# Papilio_WM.net
KiCad netlist of a schematic drawn in Altium Designer
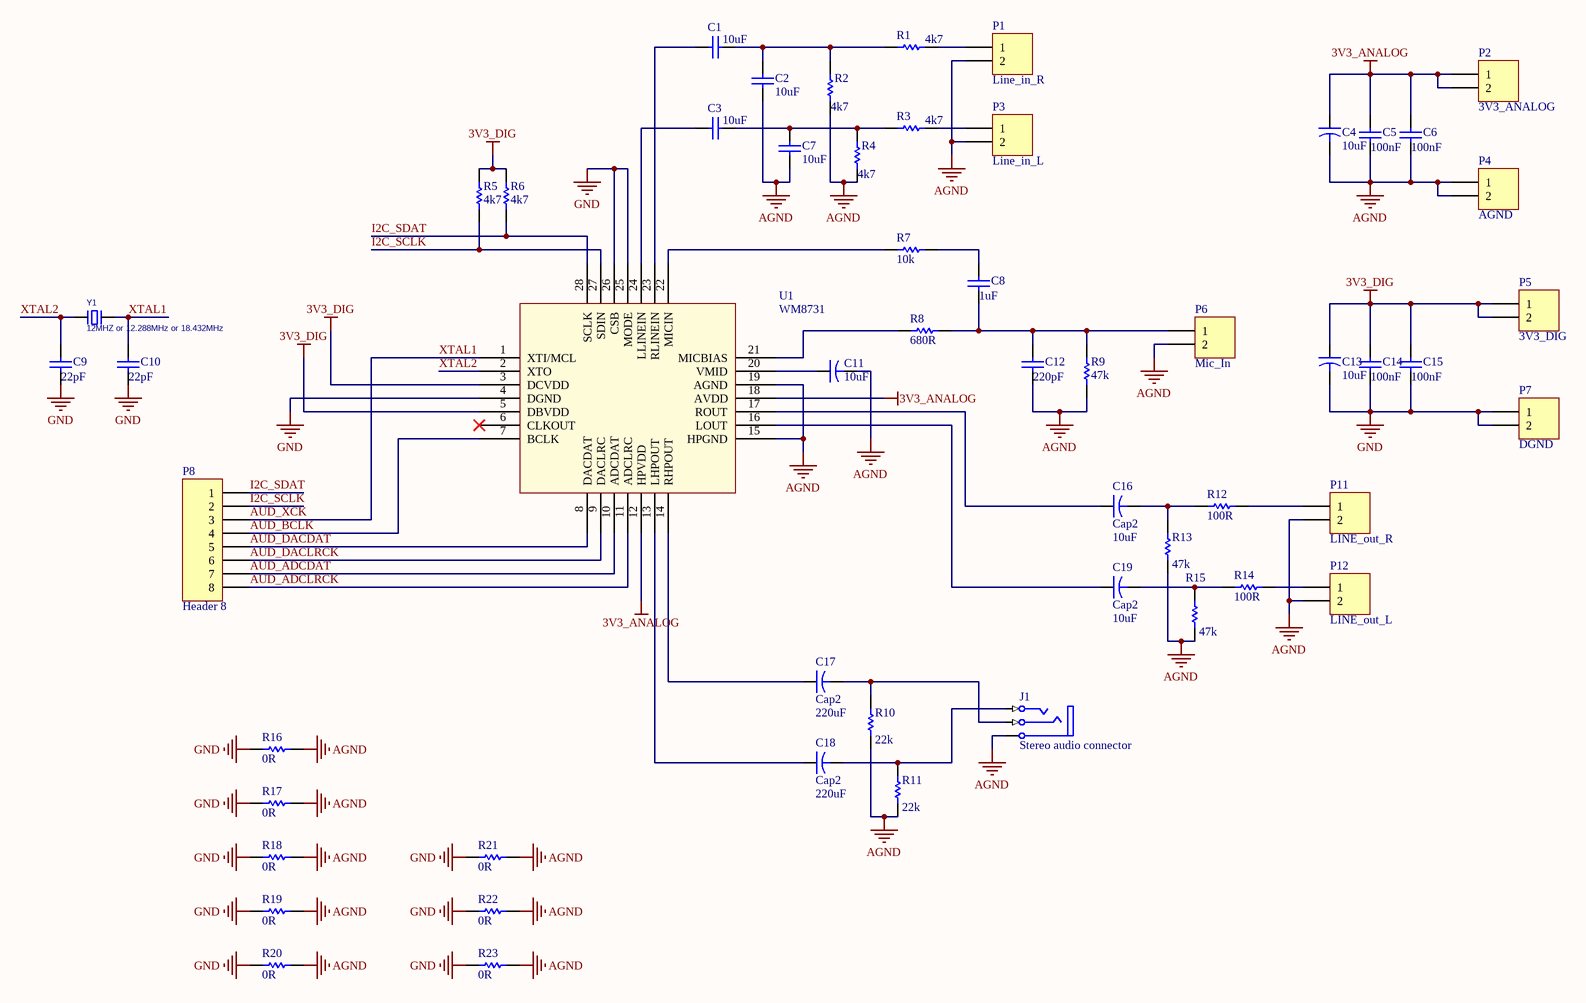
[diagram p0: Papilio_WM.SchDoc]

(export (version "E")
  (design (tool "Eeschema 10.0.6"))
  (components
    (comp (ref "C1")
      (value "10uF")
      (footprint "C0603 - rounded")
      (description "Capacitor")
      (fields (field (name "Comment") "Cap") (field (name "PUBLISHER") "Altium Limited"))
      (libsource (lib "Miscellaneous Devices") (part "Cap"))
    )
    (comp (ref "C2")
      (value "10uF")
      (footprint "C0603 - rounded")
      (description "Capacitor")
      (fields (field (name "Comment") "Cap") (field (name "PUBLISHER") "Altium Limited"))
      (libsource (lib "Miscellaneous Devices") (part "Cap"))
    )
    (comp (ref "C3")
      (value "10uF")
      (footprint "C0603 - rounded")
      (description "Capacitor")
      (fields (field (name "Comment") "Cap") (field (name "PUBLISHER") "Altium Limited"))
      (libsource (lib "Miscellaneous Devices") (part "Cap"))
    )
    (comp (ref "C4")
      (value "10uF")
      (footprint "CAP Eletrolitico 4x5.3 SMD")
      (description "Capacitor")
      (fields (field (name "Comment") "Cap2") (field (name "PUBLISHER") "Altium Limited"))
      (libsource (lib "Miscellaneous Devices") (part "Cap2"))
    )
    (comp (ref "C5")
      (value "100nF")
      (footprint "C0603 - rounded")
      (description "Capacitor")
      (fields (field (name "Comment") "Cap") (field (name "PUBLISHER") "Altium Limited"))
      (libsource (lib "Miscellaneous Devices") (part "Cap"))
    )
    (comp (ref "C6")
      (value "100nF")
      (footprint "C0603 - rounded")
      (description "Capacitor")
      (fields (field (name "Comment") "Cap") (field (name "PUBLISHER") "Altium Limited"))
      (libsource (lib "Miscellaneous Devices") (part "Cap"))
    )
    (comp (ref "C7")
      (value "10uF")
      (footprint "C0603 - rounded")
      (description "Capacitor")
      (fields (field (name "Comment") "Cap") (field (name "PUBLISHER") "Altium Limited"))
      (libsource (lib "Miscellaneous Devices") (part "Cap"))
    )
    (comp (ref "C8")
      (value "1uF")
      (footprint "C0603 - rounded")
      (description "Capacitor")
      (fields (field (name "Comment") "Cap") (field (name "PUBLISHER") "Altium Limited"))
      (libsource (lib "Miscellaneous Devices") (part "Cap"))
    )
    (comp (ref "C9")
      (value "22pF")
      (footprint "C0603 - rounded")
      (description "Capacitor")
      (fields (field (name "Comment") "Cap") (field (name "PUBLISHER") "Altium Limited"))
      (libsource (lib "Miscellaneous Devices") (part "Cap"))
    )
    (comp (ref "C10")
      (value "22pF")
      (footprint "C0603 - rounded")
      (description "Capacitor")
      (fields (field (name "Comment") "Cap") (field (name "PUBLISHER") "Altium Limited"))
      (libsource (lib "Miscellaneous Devices") (part "Cap"))
    )
    (comp (ref "C11")
      (value "10uF")
      (footprint "CAP Eletrolitico 4x5.3 SMD")
      (description "Capacitor")
      (fields (field (name "Comment") "Cap2") (field (name "PUBLISHER") "Altium Limited"))
      (libsource (lib "Miscellaneous Devices") (part "Cap2"))
    )
    (comp (ref "C12")
      (value "220pF")
      (footprint "C0603 - rounded")
      (description "Capacitor")
      (fields (field (name "Comment") "Cap") (field (name "PUBLISHER") "Altium Limited"))
      (libsource (lib "Miscellaneous Devices") (part "Cap"))
    )
    (comp (ref "C13")
      (value "10uF")
      (footprint "CAP Eletrolitico 4x5.3 SMD")
      (description "Capacitor")
      (fields (field (name "Comment") "Cap2") (field (name "PUBLISHER") "Altium Limited"))
      (libsource (lib "Miscellaneous Devices") (part "Cap2"))
    )
    (comp (ref "C14")
      (value "100nF")
      (footprint "C0603 - rounded")
      (description "Capacitor")
      (fields (field (name "Comment") "Cap") (field (name "PUBLISHER") "Altium Limited"))
      (libsource (lib "Miscellaneous Devices") (part "Cap"))
    )
    (comp (ref "C15")
      (value "100nF")
      (footprint "C0603 - rounded")
      (description "Capacitor")
      (fields (field (name "Comment") "Cap") (field (name "PUBLISHER") "Altium Limited"))
      (libsource (lib "Miscellaneous Devices") (part "Cap"))
    )
    (comp (ref "C16")
      (value "Cap2")
      (footprint "CAP Eletrolitico 4x5.3 SMD")
      (description "Capacitor")
      (fields (field (name "ALTIUM_VALUE") "10uF") (field (name "PUBLISHER") "Altium Limited"))
      (libsource (lib "Miscellaneous Devices") (part "Cap2"))
    )
    (comp (ref "C17")
      (value "Cap2")
      (footprint "CAP Eletrolitico 4x5.3 SMD")
      (description "Capacitor")
      (fields (field (name "ALTIUM_VALUE") "220uF") (field (name "PUBLISHER") "Altium Limited"))
      (libsource (lib "Miscellaneous Devices") (part "Cap2"))
    )
    (comp (ref "C18")
      (value "Cap2")
      (footprint "CAP Eletrolitico 4x5.3 SMD")
      (description "Capacitor")
      (fields (field (name "ALTIUM_VALUE") "220uF") (field (name "PUBLISHER") "Altium Limited"))
      (libsource (lib "Miscellaneous Devices") (part "Cap2"))
    )
    (comp (ref "C19")
      (value "Cap2")
      (footprint "CAP Eletrolitico 4x5.3 SMD")
      (description "Capacitor")
      (fields (field (name "ALTIUM_VALUE") "10uF") (field (name "PUBLISHER") "Altium Limited"))
      (libsource (lib "Miscellaneous Devices") (part "Cap2"))
    )
    (comp (ref "J1")
      (value "Stereo audio connector")
      (footprint "Headphone plug")
      (libsource (lib "Biblioteca_pessoal") (part "Phonejack 3"))
    )
    (comp (ref "P1")
      (value "Line_in_R")
      (footprint "HDR1X2 signed")
      (description "Header, 2-Pin")
      (fields (field (name "PUBLISHER") "Altium Limited"))
      (libsource (lib "Miscellaneous Connectors") (part "Header 2"))
    )
    (comp (ref "P2")
      (value "3V3_ANALOG")
      (footprint "HDR1X2")
      (description "Header, 2-Pin")
      (fields (field (name "PUBLISHER") "Altium Limited"))
      (libsource (lib "Miscellaneous Connectors") (part "Header 2"))
    )
    (comp (ref "P3")
      (value "Line_in_L")
      (footprint "HDR1X2 signed")
      (description "Header, 2-Pin")
      (fields (field (name "PUBLISHER") "Altium Limited"))
      (libsource (lib "Miscellaneous Connectors") (part "Header 2"))
    )
    (comp (ref "P4")
      (value "AGND")
      (footprint "HDR1X2")
      (description "Header, 2-Pin")
      (fields (field (name "PUBLISHER") "Altium Limited"))
      (libsource (lib "Miscellaneous Connectors") (part "Header 2"))
    )
    (comp (ref "P5")
      (value "3V3_DIG")
      (footprint "HDR1X2")
      (description "Header, 2-Pin")
      (fields (field (name "PUBLISHER") "Altium Limited"))
      (libsource (lib "Miscellaneous Connectors") (part "Header 2"))
    )
    (comp (ref "P6")
      (value "Mic_In")
      (footprint "HDR1X2 signed")
      (description "Header, 2-Pin")
      (fields (field (name "PUBLISHER") "Altium Limited"))
      (libsource (lib "Miscellaneous Connectors") (part "Header 2"))
    )
    (comp (ref "P7")
      (value "DGND")
      (footprint "HDR1X2")
      (description "Header, 2-Pin")
      (fields (field (name "PUBLISHER") "Altium Limited"))
      (libsource (lib "Miscellaneous Connectors") (part "Header 2"))
    )
    (comp (ref "P8")
      (value "Header 8")
      (footprint "HDR1X8")
      (description "Header, 8-Pin")
      (fields (field (name "PUBLISHER") "Altium Limited"))
      (libsource (lib "Miscellaneous Connectors") (part "Header 8"))
    )
    (comp (ref "P11")
      (value "LINE_out_R")
      (footprint "HDR1X2 signed")
      (description "Header, 2-Pin")
      (fields (field (name "PUBLISHER") "Altium Limited"))
      (libsource (lib "Miscellaneous Connectors") (part "Header 2"))
    )
    (comp (ref "P12")
      (value "LINE_out_L")
      (footprint "HDR1X2 signed")
      (description "Header, 2-Pin")
      (fields (field (name "PUBLISHER") "Altium Limited"))
      (libsource (lib "Miscellaneous Connectors") (part "Header 2"))
    )
    (comp (ref "R1")
      (value "4k7")
      (footprint "R0603 - rounded")
      (description "Resistor")
      (fields (field (name "Comment") "Res1") (field (name "PUBLISHER") "Altium Limited"))
      (libsource (lib "Miscellaneous Devices") (part "Res1"))
    )
    (comp (ref "R2")
      (value "4k7")
      (footprint "R0603 - rounded")
      (description "Resistor")
      (fields (field (name "Comment") "Res1") (field (name "PUBLISHER") "Altium Limited"))
      (libsource (lib "Miscellaneous Devices") (part "Res1"))
    )
    (comp (ref "R3")
      (value "4k7")
      (footprint "R0603 - rounded")
      (description "Resistor")
      (fields (field (name "Comment") "Res1") (field (name "PUBLISHER") "Altium Limited"))
      (libsource (lib "Miscellaneous Devices") (part "Res1"))
    )
    (comp (ref "R4")
      (value "4k7")
      (footprint "R0603 - rounded")
      (description "Resistor")
      (fields (field (name "Comment") "Res1") (field (name "PUBLISHER") "Altium Limited"))
      (libsource (lib "Miscellaneous Devices") (part "Res1"))
    )
    (comp (ref "R5")
      (value "4k7")
      (footprint "R0603 - rounded")
      (description "Resistor")
      (fields (field (name "Comment") "Res1") (field (name "PUBLISHER") "Altium Limited"))
      (libsource (lib "Miscellaneous Devices") (part "Res1"))
    )
    (comp (ref "R6")
      (value "4k7")
      (footprint "R0603 - rounded")
      (description "Resistor")
      (fields (field (name "Comment") "Res1") (field (name "PUBLISHER") "Altium Limited"))
      (libsource (lib "Miscellaneous Devices") (part "Res1"))
    )
    (comp (ref "R7")
      (value "10k")
      (footprint "R0603 - rounded")
      (description "Resistor")
      (fields (field (name "Comment") "Res1") (field (name "PUBLISHER") "Altium Limited"))
      (libsource (lib "Miscellaneous Devices") (part "Res1"))
    )
    (comp (ref "R8")
      (value "680R")
      (footprint "R0603 - rounded")
      (description "Resistor")
      (fields (field (name "Comment") "Res1") (field (name "PUBLISHER") "Altium Limited"))
      (libsource (lib "Miscellaneous Devices") (part "Res1"))
    )
    (comp (ref "R9")
      (value "47k")
      (footprint "R0603 - rounded")
      (description "Resistor")
      (fields (field (name "Comment") "Res1") (field (name "PUBLISHER") "Altium Limited"))
      (libsource (lib "Miscellaneous Devices") (part "Res1"))
    )
    (comp (ref "R10")
      (value "22k")
      (footprint "R0603 - rounded")
      (description "Resistor")
      (fields (field (name "Comment") "Res1") (field (name "PUBLISHER") "Altium Limited"))
      (libsource (lib "Miscellaneous Devices") (part "Res1"))
    )
    (comp (ref "R11")
      (value "22k")
      (footprint "R0603 - rounded")
      (description "Resistor")
      (fields (field (name "Comment") "Res1") (field (name "PUBLISHER") "Altium Limited"))
      (libsource (lib "Miscellaneous Devices") (part "Res1"))
    )
    (comp (ref "R12")
      (value "100R")
      (footprint "R0603 - rounded")
      (description "Resistor")
      (fields (field (name "Comment") "Res1") (field (name "PUBLISHER") "Altium Limited"))
      (libsource (lib "Miscellaneous Devices") (part "Res1"))
    )
    (comp (ref "R13")
      (value "47k")
      (footprint "R0603 - rounded")
      (description "Resistor")
      (fields (field (name "Comment") "Res1") (field (name "PUBLISHER") "Altium Limited"))
      (libsource (lib "Miscellaneous Devices") (part "Res1"))
    )
    (comp (ref "R14")
      (value "100R")
      (footprint "R0603 - rounded")
      (description "Resistor")
      (fields (field (name "Comment") "Res1") (field (name "PUBLISHER") "Altium Limited"))
      (libsource (lib "Miscellaneous Devices") (part "Res1"))
    )
    (comp (ref "R15")
      (value "47k")
      (footprint "R0603 - rounded")
      (description "Resistor")
      (fields (field (name "Comment") "Res1") (field (name "PUBLISHER") "Altium Limited"))
      (libsource (lib "Miscellaneous Devices") (part "Res1"))
    )
    (comp (ref "R16")
      (value "0R")
      (footprint "R0603 - rounded")
      (description "Resistor")
      (fields (field (name "Comment") "Res1") (field (name "PUBLISHER") "Altium Limited"))
      (libsource (lib "Miscellaneous Devices") (part "Res1"))
    )
    (comp (ref "R17")
      (value "0R")
      (footprint "R0603 - rounded")
      (description "Resistor")
      (fields (field (name "Comment") "Res1") (field (name "PUBLISHER") "Altium Limited"))
      (libsource (lib "Miscellaneous Devices") (part "Res1"))
    )
    (comp (ref "R18")
      (value "0R")
      (footprint "R0603 - rounded")
      (description "Resistor")
      (fields (field (name "Comment") "Res1") (field (name "PUBLISHER") "Altium Limited"))
      (libsource (lib "Miscellaneous Devices") (part "Res1"))
    )
    (comp (ref "R19")
      (value "0R")
      (footprint "R0603 - rounded")
      (description "Resistor")
      (fields (field (name "Comment") "Res1") (field (name "PUBLISHER") "Altium Limited"))
      (libsource (lib "Miscellaneous Devices") (part "Res1"))
    )
    (comp (ref "R20")
      (value "0R")
      (footprint "R0603 - rounded")
      (description "Resistor")
      (fields (field (name "Comment") "Res1") (field (name "PUBLISHER") "Altium Limited"))
      (libsource (lib "Miscellaneous Devices") (part "Res1"))
    )
    (comp (ref "R21")
      (value "0R")
      (footprint "R0603 - rounded")
      (description "Resistor")
      (fields (field (name "Comment") "Res1") (field (name "PUBLISHER") "Altium Limited"))
      (libsource (lib "Miscellaneous Devices") (part "Res1"))
    )
    (comp (ref "R22")
      (value "0R")
      (footprint "R0603 - rounded")
      (description "Resistor")
      (fields (field (name "Comment") "Res1") (field (name "PUBLISHER") "Altium Limited"))
      (libsource (lib "Miscellaneous Devices") (part "Res1"))
    )
    (comp (ref "R23")
      (value "0R")
      (footprint "R0603 - rounded")
      (description "Resistor")
      (fields (field (name "Comment") "Res1") (field (name "PUBLISHER") "Altium Limited"))
      (libsource (lib "Miscellaneous Devices") (part "Res1"))
    )
    (comp (ref "U1")
      (value "WM8731")
      (footprint "QFN24")
      (description "Audio CODEC")
      (libsource (lib "Biblioteca_pessoal") (part "WM8731"))
    )
    (comp (ref "Y1")
      (value "12MHZ or 12.288MHz or 18.432MHz")
      (footprint "XTAL")
      (libsource (lib "Biblioteca_pessoal") (part "XD-49US-A"))
    )
  )
  (nets
    (net (code "1") (name "/AUD_ADCDAT") (class "Default")
      (node (ref "P8") (pin "7") (pinfunction "7_7") (pintype "passive"))
      (node (ref "U1") (pin "10") (pinfunction "ADCDAT_10") (pintype "passive"))
    )
    (net (code "2") (name "/AUD_ADCLRCK") (class "Default")
      (node (ref "P8") (pin "8") (pinfunction "8_8") (pintype "passive"))
      (node (ref "U1") (pin "11") (pinfunction "ADCLRC_11") (pintype "passive"))
    )
    (net (code "3") (name "/AUD_BCLK") (class "Default")
      (node (ref "P8") (pin "4") (pinfunction "4_4") (pintype "passive"))
      (node (ref "U1") (pin "7") (pinfunction "BCLK_7") (pintype "passive"))
    )
    (net (code "4") (name "/AUD_DACDAT") (class "Default")
      (node (ref "P8") (pin "5") (pinfunction "5_5") (pintype "passive"))
      (node (ref "U1") (pin "8") (pinfunction "DACDAT_8") (pintype "passive"))
    )
    (net (code "5") (name "/AUD_DACLRCK") (class "Default")
      (node (ref "P8") (pin "6") (pinfunction "6_6") (pintype "passive"))
      (node (ref "U1") (pin "9") (pinfunction "DACLRC_9") (pintype "passive"))
    )
    (net (code "6") (name "/AUD_XCK") (class "Default")
      (node (ref "C10") (pin "2") (pinfunction "2_2") (pintype "passive"))
      (node (ref "P8") (pin "3") (pinfunction "3_3") (pintype "passive"))
      (node (ref "U1") (pin "1") (pinfunction "XTI/MCL_1") (pintype "passive"))
      (node (ref "Y1") (pin "2") (pinfunction "2_2") (pintype "passive"))
    )
    (net (code "7") (name "/I2C_SCLK") (class "Default")
      (node (ref "P8") (pin "2") (pinfunction "2_2") (pintype "passive"))
      (node (ref "R5") (pin "1") (pinfunction "1_1") (pintype "passive"))
      (node (ref "U1") (pin "27") (pinfunction "SDIN_27") (pintype "passive"))
    )
    (net (code "8") (name "/I2C_SDAT") (class "Default")
      (node (ref "P8") (pin "1") (pinfunction "1_1") (pintype "passive"))
      (node (ref "R6") (pin "1") (pinfunction "1_1") (pintype "passive"))
      (node (ref "U1") (pin "28") (pinfunction "SCLK_28") (pintype "passive"))
    )
    (net (code "9") (name "/XTAL2") (class "Default")
      (node (ref "C9") (pin "2") (pinfunction "2_2") (pintype "passive"))
      (node (ref "U1") (pin "2") (pinfunction "XTO_2") (pintype "passive"))
      (node (ref "Y1") (pin "1") (pinfunction "1_1") (pintype "passive"))
    )
    (net (code "10") (name "3V3_ANALOG") (class "Default")
      (node (ref "C4") (pin "1") (pinfunction "1_1") (pintype "passive"))
      (node (ref "C5") (pin "2") (pinfunction "2_2") (pintype "passive"))
      (node (ref "C6") (pin "2") (pinfunction "2_2") (pintype "passive"))
      (node (ref "P2") (pin "1") (pinfunction "1_1") (pintype "passive"))
      (node (ref "P2") (pin "2") (pinfunction "2_2") (pintype "passive"))
      (node (ref "U1") (pin "12") (pinfunction "HPVDD_12") (pintype "passive"))
      (node (ref "U1") (pin "18") (pinfunction "AVDD_18") (pintype "passive"))
    )
    (net (code "11") (name "3V3_DIG") (class "Default")
      (node (ref "C13") (pin "1") (pinfunction "1_1") (pintype "passive"))
      (node (ref "C14") (pin "2") (pinfunction "2_2") (pintype "passive"))
      (node (ref "C15") (pin "2") (pinfunction "2_2") (pintype "passive"))
      (node (ref "P5") (pin "1") (pinfunction "1_1") (pintype "passive"))
      (node (ref "P5") (pin "2") (pinfunction "2_2") (pintype "passive"))
      (node (ref "R5") (pin "2") (pinfunction "2_2") (pintype "passive"))
      (node (ref "R6") (pin "2") (pinfunction "2_2") (pintype "passive"))
      (node (ref "U1") (pin "3") (pinfunction "DCVDD_3") (pintype "passive"))
      (node (ref "U1") (pin "5") (pinfunction "DBVDD_5") (pintype "passive"))
    )
    (net (code "12") (name "AGND") (class "Default")
      (node (ref "C11") (pin "2") (pinfunction "2_2") (pintype "passive"))
      (node (ref "C12") (pin "1") (pinfunction "1_1") (pintype "passive"))
      (node (ref "C2") (pin "1") (pinfunction "1_1") (pintype "passive"))
      (node (ref "C4") (pin "2") (pinfunction "2_2") (pintype "passive"))
      (node (ref "C5") (pin "1") (pinfunction "1_1") (pintype "passive"))
      (node (ref "C6") (pin "1") (pinfunction "1_1") (pintype "passive"))
      (node (ref "C7") (pin "1") (pinfunction "1_1") (pintype "passive"))
      (node (ref "J1") (pin "3") (pinfunction "S_3") (pintype "power_in"))
      (node (ref "P1") (pin "2") (pinfunction "2_2") (pintype "passive"))
      (node (ref "P11") (pin "2") (pinfunction "2_2") (pintype "passive"))
      (node (ref "P12") (pin "2") (pinfunction "2_2") (pintype "passive"))
      (node (ref "P3") (pin "2") (pinfunction "2_2") (pintype "passive"))
      (node (ref "P4") (pin "1") (pinfunction "1_1") (pintype "passive"))
      (node (ref "P4") (pin "2") (pinfunction "2_2") (pintype "passive"))
      (node (ref "P6") (pin "2") (pinfunction "2_2") (pintype "passive"))
      (node (ref "R10") (pin "1") (pinfunction "1_1") (pintype "passive"))
      (node (ref "R11") (pin "1") (pinfunction "1_1") (pintype "passive"))
      (node (ref "R13") (pin "1") (pinfunction "1_1") (pintype "passive"))
      (node (ref "R15") (pin "1") (pinfunction "1_1") (pintype "passive"))
      (node (ref "R16") (pin "1") (pinfunction "1_1") (pintype "passive"))
      (node (ref "R17") (pin "1") (pinfunction "1_1") (pintype "passive"))
      (node (ref "R18") (pin "1") (pinfunction "1_1") (pintype "passive"))
      (node (ref "R19") (pin "1") (pinfunction "1_1") (pintype "passive"))
      (node (ref "R2") (pin "1") (pinfunction "1_1") (pintype "passive"))
      (node (ref "R20") (pin "1") (pinfunction "1_1") (pintype "passive"))
      (node (ref "R21") (pin "1") (pinfunction "1_1") (pintype "passive"))
      (node (ref "R22") (pin "1") (pinfunction "1_1") (pintype "passive"))
      (node (ref "R23") (pin "1") (pinfunction "1_1") (pintype "passive"))
      (node (ref "R4") (pin "1") (pinfunction "1_1") (pintype "passive"))
      (node (ref "R9") (pin "2") (pinfunction "2_2") (pintype "passive"))
      (node (ref "U1") (pin "15") (pinfunction "HPGND_15") (pintype "passive"))
      (node (ref "U1") (pin "19") (pinfunction "AGND_19") (pintype "passive"))
    )
    (net (code "13") (name "GND") (class "Default")
      (node (ref "C10") (pin "1") (pinfunction "1_1") (pintype "passive"))
      (node (ref "C13") (pin "2") (pinfunction "2_2") (pintype "passive"))
      (node (ref "C14") (pin "1") (pinfunction "1_1") (pintype "passive"))
      (node (ref "C15") (pin "1") (pinfunction "1_1") (pintype "passive"))
      (node (ref "C9") (pin "1") (pinfunction "1_1") (pintype "passive"))
      (node (ref "P7") (pin "1") (pinfunction "1_1") (pintype "passive"))
      (node (ref "P7") (pin "2") (pinfunction "2_2") (pintype "passive"))
      (node (ref "R16") (pin "2") (pinfunction "2_2") (pintype "passive"))
      (node (ref "R17") (pin "2") (pinfunction "2_2") (pintype "passive"))
      (node (ref "R18") (pin "2") (pinfunction "2_2") (pintype "passive"))
      (node (ref "R19") (pin "2") (pinfunction "2_2") (pintype "passive"))
      (node (ref "R20") (pin "2") (pinfunction "2_2") (pintype "passive"))
      (node (ref "R21") (pin "2") (pinfunction "2_2") (pintype "passive"))
      (node (ref "R22") (pin "2") (pinfunction "2_2") (pintype "passive"))
      (node (ref "R23") (pin "2") (pinfunction "2_2") (pintype "passive"))
      (node (ref "U1") (pin "25") (pinfunction "MODE_25") (pintype "passive"))
      (node (ref "U1") (pin "26") (pinfunction "CSB_26") (pintype "passive"))
      (node (ref "U1") (pin "4") (pinfunction "DGND_4") (pintype "passive"))
    )
    (net (code "14") (name "Net-(C1-Pad2)") (class "Default")
      (node (ref "C1") (pin "2") (pinfunction "2_2") (pintype "passive"))
      (node (ref "C2") (pin "2") (pinfunction "2_2") (pintype "passive"))
      (node (ref "R1") (pin "2") (pinfunction "2_2") (pintype "passive"))
      (node (ref "R2") (pin "2") (pinfunction "2_2") (pintype "passive"))
    )
    (net (code "15") (name "Net-(C3-Pad2)") (class "Default")
      (node (ref "C3") (pin "2") (pinfunction "2_2") (pintype "passive"))
      (node (ref "C7") (pin "2") (pinfunction "2_2") (pintype "passive"))
      (node (ref "R3") (pin "2") (pinfunction "2_2") (pintype "passive"))
      (node (ref "R4") (pin "2") (pinfunction "2_2") (pintype "passive"))
    )
    (net (code "16") (name "Net-(C8-Pad2)") (class "Default")
      (node (ref "C8") (pin "2") (pinfunction "2_2") (pintype "passive"))
      (node (ref "R7") (pin "1") (pinfunction "1_1") (pintype "passive"))
    )
    (net (code "17") (name "Net-(C12-Pad2)") (class "Default")
      (node (ref "C12") (pin "2") (pinfunction "2_2") (pintype "passive"))
      (node (ref "C8") (pin "1") (pinfunction "1_1") (pintype "passive"))
      (node (ref "P6") (pin "1") (pinfunction "1_1") (pintype "passive"))
      (node (ref "R8") (pin "1") (pinfunction "1_1") (pintype "passive"))
      (node (ref "R9") (pin "1") (pinfunction "1_1") (pintype "passive"))
    )
    (net (code "18") (name "Net-(C16-Pad2)") (class "Default")
      (node (ref "C16") (pin "2") (pinfunction "2_2") (pintype "passive"))
      (node (ref "R12") (pin "2") (pinfunction "2_2") (pintype "passive"))
      (node (ref "R13") (pin "2") (pinfunction "2_2") (pintype "passive"))
    )
    (net (code "19") (name "Net-(C19-Pad2)") (class "Default")
      (node (ref "C19") (pin "2") (pinfunction "2_2") (pintype "passive"))
      (node (ref "R14") (pin "2") (pinfunction "2_2") (pintype "passive"))
      (node (ref "R15") (pin "2") (pinfunction "2_2") (pintype "passive"))
    )
    (net (code "20") (name "Net-(J1-R)") (class "Default")
      (node (ref "C17") (pin "2") (pinfunction "2_2") (pintype "passive"))
      (node (ref "J1") (pin "5") (pinfunction "R_5") (pintype "input"))
      (node (ref "R10") (pin "2") (pinfunction "2_2") (pintype "passive"))
    )
    (net (code "21") (name "Net-(J1-T)") (class "Default")
      (node (ref "C18") (pin "2") (pinfunction "2_2") (pintype "passive"))
      (node (ref "J1") (pin "1") (pinfunction "T_1") (pintype "input"))
      (node (ref "R11") (pin "2") (pinfunction "2_2") (pintype "passive"))
    )
    (net (code "22") (name "Net-(P1-Pad1)") (class "Default")
      (node (ref "P1") (pin "1") (pinfunction "1_1") (pintype "passive"))
      (node (ref "R1") (pin "1") (pinfunction "1_1") (pintype "passive"))
    )
    (net (code "23") (name "Net-(P3-Pad1)") (class "Default")
      (node (ref "P3") (pin "1") (pinfunction "1_1") (pintype "passive"))
      (node (ref "R3") (pin "1") (pinfunction "1_1") (pintype "passive"))
    )
    (net (code "24") (name "Net-(P11-Pad1)") (class "Default")
      (node (ref "P11") (pin "1") (pinfunction "1_1") (pintype "passive"))
      (node (ref "R12") (pin "1") (pinfunction "1_1") (pintype "passive"))
    )
    (net (code "25") (name "Net-(P12-Pad1)") (class "Default")
      (node (ref "P12") (pin "1") (pinfunction "1_1") (pintype "passive"))
      (node (ref "R14") (pin "1") (pinfunction "1_1") (pintype "passive"))
    )
    (net (code "26") (name "Net-(U1-LHPOUT)") (class "Default")
      (node (ref "C18") (pin "1") (pinfunction "1_1") (pintype "passive"))
      (node (ref "U1") (pin "13") (pinfunction "LHPOUT_13") (pintype "passive"))
    )
    (net (code "27") (name "Net-(U1-LLINEIN)") (class "Default")
      (node (ref "C3") (pin "1") (pinfunction "1_1") (pintype "passive"))
      (node (ref "U1") (pin "24") (pinfunction "LLINEIN_24") (pintype "passive"))
    )
    (net (code "28") (name "Net-(U1-LOUT)") (class "Default")
      (node (ref "C19") (pin "1") (pinfunction "1_1") (pintype "passive"))
      (node (ref "U1") (pin "16") (pinfunction "LOUT_16") (pintype "passive"))
    )
    (net (code "29") (name "Net-(U1-MICBIAS)") (class "Default")
      (node (ref "R8") (pin "2") (pinfunction "2_2") (pintype "passive"))
      (node (ref "U1") (pin "21") (pinfunction "MICBIAS_21") (pintype "passive"))
    )
    (net (code "30") (name "Net-(U1-MICIN)") (class "Default")
      (node (ref "R7") (pin "2") (pinfunction "2_2") (pintype "passive"))
      (node (ref "U1") (pin "22") (pinfunction "MICIN_22") (pintype "passive"))
    )
    (net (code "31") (name "Net-(U1-RHPOUT)") (class "Default")
      (node (ref "C17") (pin "1") (pinfunction "1_1") (pintype "passive"))
      (node (ref "U1") (pin "14") (pinfunction "RHPOUT_14") (pintype "passive"))
    )
    (net (code "32") (name "Net-(U1-RLINEIN)") (class "Default")
      (node (ref "C1") (pin "1") (pinfunction "1_1") (pintype "passive"))
      (node (ref "U1") (pin "23") (pinfunction "RLINEIN_23") (pintype "passive"))
    )
    (net (code "33") (name "Net-(U1-ROUT)") (class "Default")
      (node (ref "C16") (pin "1") (pinfunction "1_1") (pintype "passive"))
      (node (ref "U1") (pin "17") (pinfunction "ROUT_17") (pintype "passive"))
    )
    (net (code "34") (name "Net-(U1-VMID)") (class "Default")
      (node (ref "C11") (pin "1") (pinfunction "1_1") (pintype "passive"))
      (node (ref "U1") (pin "20") (pinfunction "VMID_20") (pintype "passive"))
    )
    (net (code "35") (name "unconnected-(U1-CLKOUT-Pad6)") (class "Default")
      (node (ref "U1") (pin "6") (pinfunction "CLKOUT_6") (pintype "passive+no_connect"))
    )
  )
)
